# wisp-5-afe.net
KiCad netlist of a schematic drawn in Altium Designer
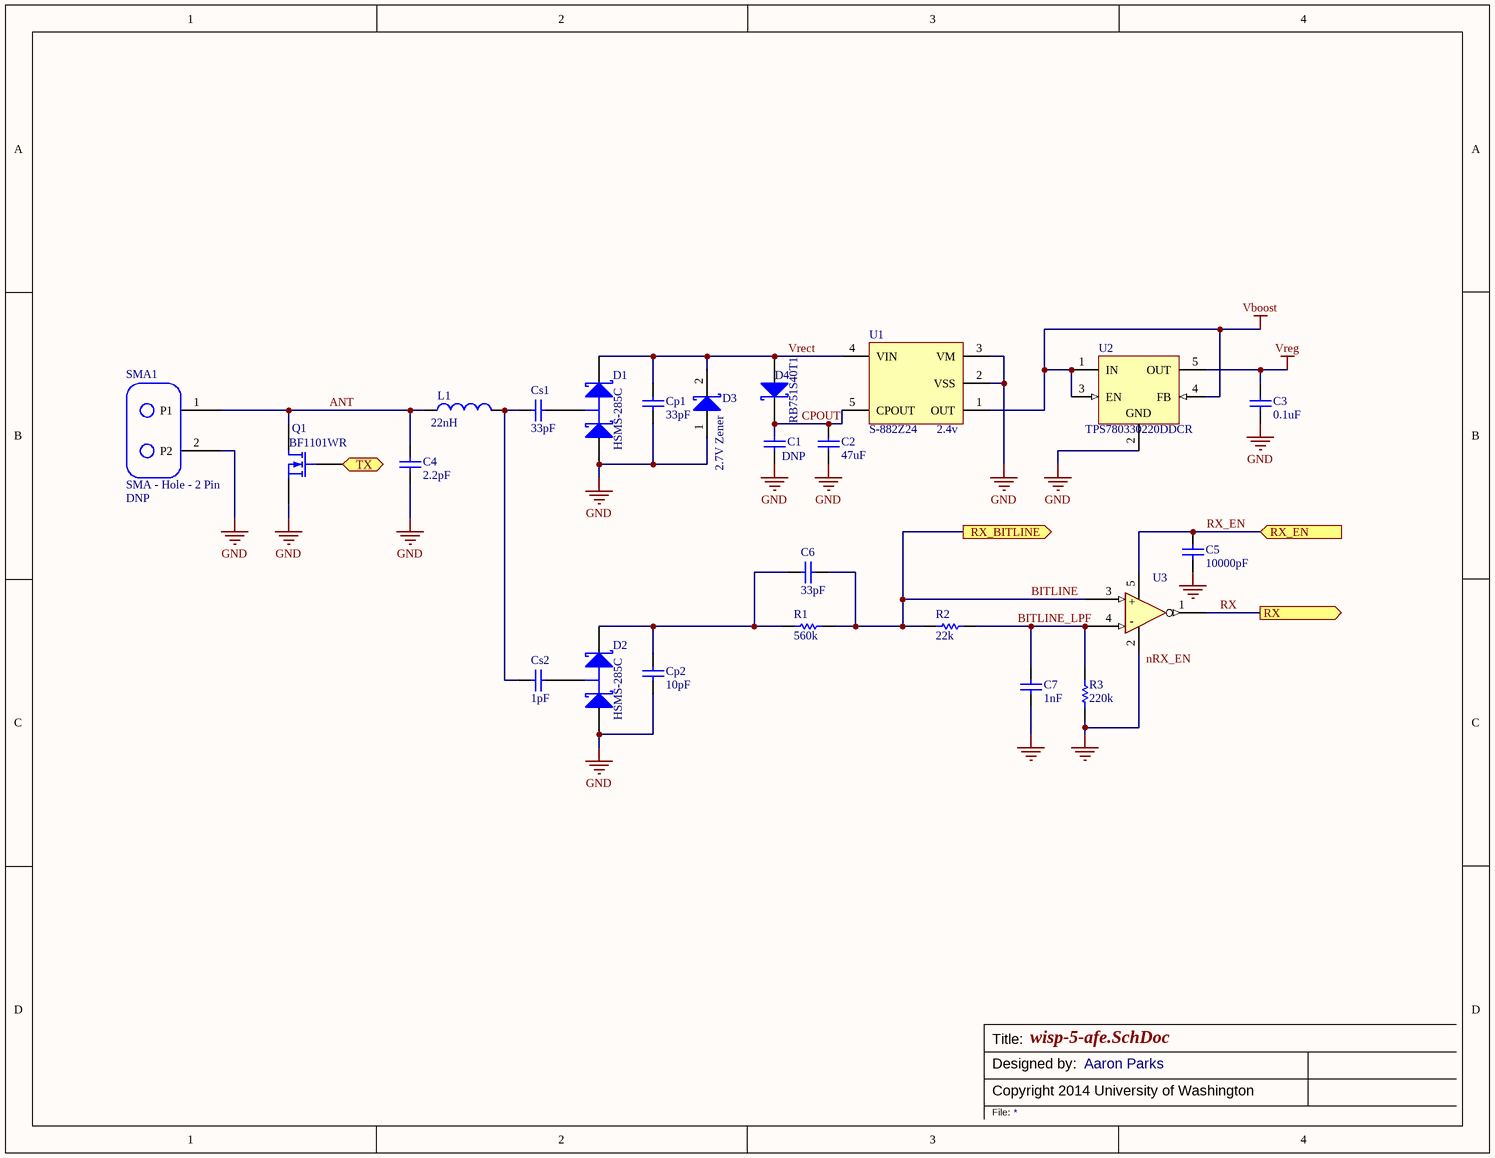
[diagram p0: wisp-5-afe.SchDoc]

(export (version "E")
  (design (tool "Eeschema 10.0.6"))
  (components
    (comp (ref "C1")
      (value "Cap")
      (footprint "0805")
      (description "Ceramic Capacitor (Surface Mount)")
      (fields (field (name "DNP") "DNP"))
      (libsource (lib "WISP_AD10") (part "Cap"))
    )
    (comp (ref "C2")
      (value "47uF")
      (footprint "0805")
      (description "Ceramic Capacitor (Surface Mount)")
      (fields
        (field (name "DIGI-KEY PART NUMBER") "1276-2420-1-ND")
        (field (name "MANUFACTURER") "Samsung Electro-Mechanics")
      )
      (libsource (lib "WISP_AD10") (part "Cap"))
    )
    (comp (ref "C3")
      (value "0.1uF")
      (footprint "0402")
      (description "Ceramic Capacitor (Surface Mount)")
      (fields (field (name "DIGI-KEY PART NUMBER") "490-3261-1-ND") (field (name "MANUFACTURER") "Murata"))
      (libsource (lib "WISP_AD10") (part "Cap"))
    )
    (comp (ref "C4")
      (value "2.2pF")
      (footprint "0402")
      (description "Ceramic Capacitor (Surface Mount)")
      (fields (field (name "DIGI-KEY PART NUMBER") "712-1289-1-ND") (field (name "MANUFACTURER") "Johanson"))
      (libsource (lib "WISP_AD10") (part "Cap"))
    )
    (comp (ref "C5")
      (value "10000pF")
      (footprint "0402")
      (description "Ceramic Capacitor (Surface Mount)")
      (fields
        (field (name "DIGI-KEY PART NUMBER") "1276-1502-1-ND")
        (field (name "MANUFACTURER") "Generic Ceramic Chip Cap (TBD)")
      )
      (libsource (lib "WISP_AD10") (part "Cap"))
    )
    (comp (ref "C6")
      (value "33pF")
      (footprint "0402")
      (description "Ceramic Capacitor (Surface Mount)")
      (fields (field (name "DIGI-KEY PART NUMBER") "712-1298-1-ND") (field (name "MANUFACTURER") "Johanson"))
      (libsource (lib "WISP_AD10") (part "Cap"))
    )
    (comp (ref "C7")
      (value "1nF")
      (footprint "0402")
      (description "Ceramic Capacitor (Surface Mount)")
      (fields
        (field (name "DIGI-KEY PART NUMBER") "490-3244-1-ND")
        (field (name "MANUFACTURER") "Generic Ceramic Chip Cap (TBD)")
      )
      (libsource (lib "WISP_AD10") (part "Cap"))
    )
    (comp (ref "Cp1")
      (value "33pF")
      (footprint "0402")
      (description "Ceramic Capacitor (Surface Mount)")
      (fields (field (name "DIGI-KEY PART NUMBER") "712-1298-1-ND") (field (name "MANUFACTURER") "Johanson"))
      (libsource (lib "WISP_AD10") (part "Cap"))
    )
    (comp (ref "Cp2")
      (value "10pF")
      (footprint "0402")
      (description "Ceramic Capacitor (Surface Mount)")
      (fields (field (name "DIGI-KEY PART NUMBER") "712-1253-1-ND") (field (name "MANUFACTURER") "Johanson"))
      (libsource (lib "WISP_AD10") (part "Cap"))
    )
    (comp (ref "Cs1")
      (value "33pF")
      (footprint "0402")
      (description "Ceramic Capacitor (Surface Mount)")
      (fields (field (name "DIGI-KEY PART NUMBER") "712-1298-1-ND") (field (name "MANUFACTURER") "Johanson"))
      (libsource (lib "WISP_AD10") (part "Cap"))
    )
    (comp (ref "Cs2")
      (value "1pF")
      (footprint "0402")
      (description "Ceramic Capacitor (Surface Mount)")
      (fields (field (name "DIGI-KEY PART NUMBER") "712-1266-1-ND") (field (name "MANUFACTURER") "Johanson"))
      (libsource (lib "WISP_AD10") (part "Cap"))
    )
    (comp (ref "D1")
      (value "HSMS-285C")
      (footprint "SOT-323, HSMS-285C")
      (description "Agilent Schottky Diode, Two in Series, Small Package SOT-323")
      (fields
        (field (name "DIGI-KEY PART NUMBER") "516-2558-ND")
        (field (name "MANUFACTURER") "Avago Technologies US Inc.")
      )
      (libsource (lib "WISP_AD10") (part "HSMS-285C"))
    )
    (comp (ref "D2")
      (value "HSMS-285C")
      (footprint "SOT-323, HSMS-285C")
      (description "Agilent Schottky Diode, Two in Series, Small Package SOT-323")
      (fields
        (field (name "DIGI-KEY PART NUMBER") "516-2558-ND")
        (field (name "MANUFACTURER") "Avago Technologies US Inc.")
      )
      (libsource (lib "WISP_AD10") (part "HSMS-285C"))
    )
    (comp (ref "D3")
      (value "2.7V Zener")
      (footprint "DIOD-SOD-123-2_V")
      (fields
        (field (name "MANUFACTURER PART NUMBER") "MMSZ4682T1G")
        (field (name "MANUFACTURER") "ON Semiconductor")
        (field (name "DIGI-KEY PART NUMBER") "MMSZ4682T1GOSCT-ND")
      )
      (libsource (lib "Altium Content Vault") (part "CMP-0303-00003-1"))
    )
    (comp (ref "D4")
      (value "RB751S40T1")
      (footprint "SOD-523")
      (description "Schottky Diode")
      (fields
        (field (name "MANUFACTURER PART NUMBER") "RB751S40T1G")
        (field (name "MANUFACTURER") "ON Semiconductor")
      )
      (libsource (lib "WISP_AD10") (part "RB751S40T1"))
    )
    (comp (ref "L1")
      (value "22nH")
      (footprint "0603")
      (description "Inductor (Surface Mount)")
      (fields
        (field (name "MANUFACTURER") "Coilcraft (http://www.coilcraft.com/0402cs.cfm)")
        (field (name "MANUFACTURER PART NUMBER") "0402CS-16NX_LU")
      )
      (libsource (lib "WISP_AD10") (part "Ind"))
    )
    (comp (ref "Q1")
      (value "BF1101WR")
      (footprint "SOT343R")
      (description "N-Channel Dual-Gate Mos-Fets MOSFET, SOT343R")
      (fields
        (field (name "DIGI-KEY PART NUMBER") "568-6140-1-ND")
        (field (name "MANUFACTURER PART NUMBER") "BF1101WR,115")
      )
      (libsource (lib "WISP_AD10") (part "BF1101WR"))
    )
    (comp (ref "R1")
      (value "560k")
      (footprint "0402")
      (description "Chip Resistor (Surface Mount)")
      (fields
        (field (name "MANUFACTURER") "Panasonic")
        (field (name "MANUFACTURER PART NUMBER") "ERJ-2RKF5603X")
      )
      (libsource (lib "WISP_AD10") (part "Res"))
    )
    (comp (ref "R2")
      (value "22k")
      (footprint "0402")
      (description "Chip Resistor (Surface Mount)")
      (fields
        (field (name "MANUFACTURER") "Panasonic")
        (field (name "MANUFACTURER PART NUMBER") "ERJ-2RKF2202X")
      )
      (libsource (lib "WISP_AD10") (part "Res"))
    )
    (comp (ref "R3")
      (value "220k")
      (footprint "0402")
      (description "Chip Resistor (Surface Mount)")
      (fields
        (field (name "MANUFACTURER") "Panasonic")
        (field (name "MANUFACTURER PART NUMBER") "ERJ-2RKF2203X")
      )
      (libsource (lib "WISP_AD10") (part "Res"))
    )
    (comp (ref "SMA1")
      (value "SMA - Hole - 2 Pin")
      (footprint "SMA - Hole - 2 Pin")
      (description "Two pin SMA connector wisp")
      (fields (field (name "DNP") "DNP"))
      (libsource (lib "WISP_AD10") (part "SMA - Hole - 2 Pin"))
    )
    (comp (ref "U1")
      (value "S-882Z24")
      (footprint "SOT23-5")
      (description "ULTRA-LOW VOLTAGE OPERATION CHARGE PUMP IC  FOR STEP-UP DC-DC CONVERTER STARTUP")
      (fields
        (field (name "DIGI-KEY PART NUMBER") "S-882Z24-M5T1G-ND")
        (field (name "MANUFACTURER") "Seiko Instruments")
        (field (name "ALTIUM_VALUE") "2.4v")
      )
      (libsource (lib "WISP_AD10") (part "S-882Zxx"))
    )
    (comp (ref "U2")
      (value "TPS780330220DDCR")
      (footprint "TI-DDC5_L")
      (fields
        (field (name "MANUFACTURER") "Texas Instruments")
        (field (name "DIGI-KEY PART NUMBER") "296-23332-1-ND")
      )
      (libsource (lib "Altium Content Vault") (part "CMP-0394-01119-1"))
    )
    (comp (ref "U3")
      (value "Comparator")
      (footprint "SC70-5")
      (description "Comparator: On Semi 10uA Comparator")
      (fields
        (field (name "DIGI-KEY PART NUMBER") "NCS2200SQ2T2GOSCT-ND")
        (field (name "MANUFACTURER") "ON Semiconductor")
      )
      (libsource (lib "WISP_AD10") (part "NCS2200"))
    )
  )
  (nets
    (net (code "1") (name "/ANT") (class "Default")
      (node (ref "C4") (pin "2") (pinfunction "2_2") (pintype "passive"))
      (node (ref "L1") (pin "1") (pinfunction "1_1") (pintype "passive"))
      (node (ref "Q1") (pin "2") (pinfunction "D_2") (pintype "passive"))
      (node (ref "SMA1") (pin "1") (pinfunction "P1_1") (pintype "passive"))
    )
    (net (code "2") (name "/BITLINE") (class "Default")
      (node (ref "C6") (pin "2") (pinfunction "2_2") (pintype "passive"))
      (node (ref "R1") (pin "1") (pinfunction "1_1") (pintype "passive"))
      (node (ref "R2") (pin "2") (pinfunction "2_2") (pintype "passive"))
      (node (ref "U3") (pin "3") (pinfunction "IN+_3") (pintype "input"))
    )
    (net (code "3") (name "/BITLINE_LPF") (class "Default")
      (node (ref "C7") (pin "1") (pinfunction "1_1") (pintype "passive"))
      (node (ref "R2") (pin "1") (pinfunction "1_1") (pintype "passive"))
      (node (ref "R3") (pin "1") (pinfunction "1_1") (pintype "passive"))
      (node (ref "U3") (pin "4") (pinfunction "In-_4") (pintype "input"))
    )
    (net (code "4") (name "/CPOUT") (class "Default")
      (node (ref "C1") (pin "1") (pinfunction "1_1") (pintype "passive"))
      (node (ref "C2") (pin "1") (pinfunction "1_1") (pintype "passive"))
      (node (ref "D4") (pin "1") (pinfunction "C_1") (pintype "passive"))
      (node (ref "U1") (pin "5") (pinfunction "CPOUT_5") (pintype "passive"))
    )
    (net (code "5") (name "/RX") (class "Default")
      (node (ref "U3") (pin "1") (pinfunction "OUT_1") (pintype "output"))
    )
    (net (code "6") (name "/RX_EN") (class "Default")
      (node (ref "C5") (pin "1") (pinfunction "1_1") (pintype "passive"))
      (node (ref "U3") (pin "5") (pinfunction "VDD_5") (pintype "passive"))
    )
    (net (code "7") (name "/TX") (class "Default")
      (node (ref "Q1") (pin "3") (pinfunction "G_3") (pintype "passive"))
    )
    (net (code "8") (name "/Vrect") (class "Default")
      (node (ref "Cp1") (pin "1") (pinfunction "1_1") (pintype "passive"))
      (node (ref "D1") (pin "2") (pinfunction "K_2") (pintype "passive"))
      (node (ref "D3") (pin "2") (pinfunction "K_2") (pintype "passive"))
      (node (ref "D4") (pin "2") (pinfunction "A_2") (pintype "passive"))
      (node (ref "U1") (pin "4") (pinfunction "VIN_4") (pintype "passive"))
    )
    (net (code "10") (name "GND") (class "Default")
      (node (ref "C1") (pin "2") (pinfunction "2_2") (pintype "passive"))
      (node (ref "C2") (pin "2") (pinfunction "2_2") (pintype "passive"))
      (node (ref "C3") (pin "1") (pinfunction "1_1") (pintype "passive"))
      (node (ref "C4") (pin "1") (pinfunction "1_1") (pintype "passive"))
      (node (ref "C5") (pin "2") (pinfunction "2_2") (pintype "passive"))
      (node (ref "C7") (pin "2") (pinfunction "2_2") (pintype "passive"))
      (node (ref "Cp1") (pin "2") (pinfunction "2_2") (pintype "passive"))
      (node (ref "Cp2") (pin "2") (pinfunction "2_2") (pintype "passive"))
      (node (ref "D1") (pin "1") (pinfunction "A_1") (pintype "passive"))
      (node (ref "D2") (pin "1") (pinfunction "A_1") (pintype "passive"))
      (node (ref "D3") (pin "1") (pinfunction "A_1") (pintype "passive"))
      (node (ref "Q1") (pin "1") (pinfunction "S_1") (pintype "passive"))
      (node (ref "R3") (pin "2") (pinfunction "2_2") (pintype "passive"))
      (node (ref "SMA1") (pin "2") (pinfunction "P2_2") (pintype "passive"))
      (node (ref "U1") (pin "2") (pinfunction "VSS_2") (pintype "passive"))
      (node (ref "U1") (pin "3") (pinfunction "VM_3") (pintype "passive"))
      (node (ref "U2") (pin "2") (pinfunction "GND_2") (pintype "power_in"))
      (node (ref "U3") (pin "2") (pinfunction "Gnd_2") (pintype "power_in"))
    )
    (net (code "11") (name "Net-(Cs1-Pad1)") (class "Default")
      (node (ref "Cs1") (pin "1") (pinfunction "1_1") (pintype "passive"))
      (node (ref "Cs2") (pin "1") (pinfunction "1_1") (pintype "passive"))
      (node (ref "L1") (pin "2") (pinfunction "2_2") (pintype "passive"))
    )
    (net (code "12") (name "Net-(D1-C)") (class "Default")
      (node (ref "Cs1") (pin "2") (pinfunction "2_2") (pintype "passive"))
      (node (ref "D1") (pin "3") (pinfunction "C_3") (pintype "passive"))
    )
    (net (code "13") (name "Net-(D2-C)") (class "Default")
      (node (ref "Cs2") (pin "2") (pinfunction "2_2") (pintype "passive"))
      (node (ref "D2") (pin "3") (pinfunction "C_3") (pintype "passive"))
    )
    (net (code "14") (name "Net-(D2-K)") (class "Default")
      (node (ref "C6") (pin "1") (pinfunction "1_1") (pintype "passive"))
      (node (ref "Cp2") (pin "1") (pinfunction "1_1") (pintype "passive"))
      (node (ref "D2") (pin "2") (pinfunction "K_2") (pintype "passive"))
      (node (ref "R1") (pin "2") (pinfunction "2_2") (pintype "passive"))
    )
    (net (code "15") (name "Vboost") (class "Default")
      (node (ref "U1") (pin "1") (pinfunction "OUT_1") (pintype "passive"))
      (node (ref "U2") (pin "1") (pinfunction "IN_1") (pintype "power_in"))
      (node (ref "U2") (pin "3") (pinfunction "EN_3") (pintype "input"))
      (node (ref "U2") (pin "4") (pinfunction "FB_4") (pintype "input"))
    )
    (net (code "16") (name "Vreg") (class "Default")
      (node (ref "C3") (pin "2") (pinfunction "2_2") (pintype "passive"))
      (node (ref "U2") (pin "5") (pinfunction "OUT_5") (pintype "power_in"))
    )
  )
)
